# DIP_Switch.net
KiCad netlist of a schematic drawn in Altium Designer
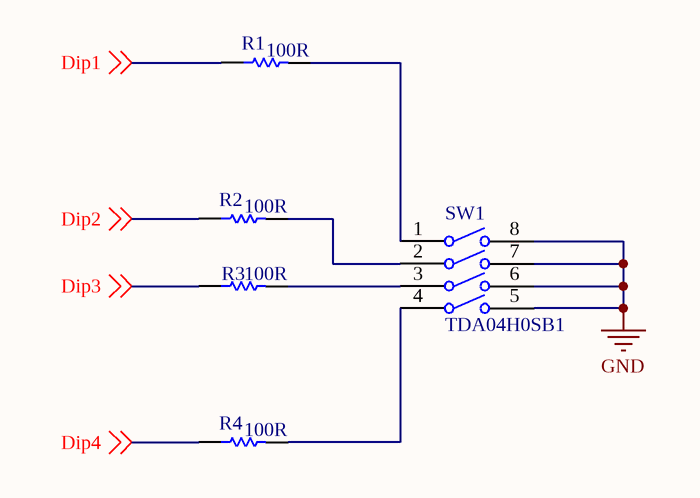
[diagram p0: DIP Switch.SchDoc]

(export (version "E")
  (design (tool "Eeschema 10.0.6"))
  (components
    (comp (ref "R1")
      (value "100R")
      (footprint "RESC0805(2012)_N")
      (description "120R 0.125W 5% 0805 (2012 Metric)  SMD")
      (fields (field (name "TOLERANCE") "5 %") (field (name "POWER") "0.125 W"))
      (libsource (lib "Husky Robotics Standard Library 2019-2020") (part "120R 5% 0805"))
    )
    (comp (ref "R2")
      (value "100R")
      (footprint "RESC0805(2012)_N")
      (description "120R 0.125W 5% 0805 (2012 Metric)  SMD")
      (fields (field (name "TOLERANCE") "5 %") (field (name "POWER") "0.125 W"))
      (libsource (lib "Husky Robotics Standard Library 2019-2020") (part "120R 5% 0805"))
    )
    (comp (ref "R3")
      (value "100R")
      (footprint "RESC0805(2012)_N")
      (description "120R 0.125W 5% 0805 (2012 Metric)  SMD")
      (fields (field (name "TOLERANCE") "5 %") (field (name "POWER") "0.125 W"))
      (libsource (lib "Husky Robotics Standard Library 2019-2020") (part "120R 5% 0805"))
    )
    (comp (ref "R4")
      (value "100R")
      (footprint "RESC0805(2012)_N")
      (description "120R 0.125W 5% 0805 (2012 Metric)  SMD")
      (fields (field (name "TOLERANCE") "5 %") (field (name "POWER") "0.125 W"))
      (libsource (lib "Husky Robotics Standard Library 2019-2020") (part "120R 5% 0805"))
    )
    (comp (ref "SW1")
      (value "TDA04H0SB1")
      (footprint "CKCP-TDA04H0SB1R_V")
      (libsource (lib "Husky Robotics Standard Library 2019-2020") (part "SMD Half-Pitch Dip Switch Array"))
    )
  )
  (nets
    (net (code "1") (name "Dip1") (class "Default")
      (node (ref "R1") (pin "1") (pinfunction "1_1") (pintype "passive"))
    )
    (net (code "2") (name "Dip2") (class "Default")
      (node (ref "R2") (pin "1") (pinfunction "1_1") (pintype "passive"))
    )
    (net (code "3") (name "Dip3") (class "Default")
      (node (ref "R3") (pin "1") (pinfunction "1_1") (pintype "passive"))
    )
    (net (code "4") (name "Dip4") (class "Default")
      (node (ref "R4") (pin "1") (pinfunction "1_1") (pintype "passive"))
    )
    (net (code "5") (name "GND") (class "Default")
      (node (ref "SW1") (pin "5") (pinfunction "5_5") (pintype "passive"))
      (node (ref "SW1") (pin "6") (pinfunction "6_6") (pintype "passive"))
      (node (ref "SW1") (pin "7") (pinfunction "7_7") (pintype "passive"))
      (node (ref "SW1") (pin "8") (pinfunction "8_8") (pintype "passive"))
    )
    (net (code "6") (name "Net-(R1-Pad2)") (class "Default")
      (node (ref "R1") (pin "2") (pinfunction "2_2") (pintype "passive"))
      (node (ref "SW1") (pin "1") (pinfunction "1_1") (pintype "passive"))
    )
    (net (code "7") (name "Net-(R2-Pad2)") (class "Default")
      (node (ref "R2") (pin "2") (pinfunction "2_2") (pintype "passive"))
      (node (ref "SW1") (pin "2") (pinfunction "2_2") (pintype "passive"))
    )
    (net (code "8") (name "Net-(R3-Pad2)") (class "Default")
      (node (ref "R3") (pin "2") (pinfunction "2_2") (pintype "passive"))
      (node (ref "SW1") (pin "3") (pinfunction "3_3") (pintype "passive"))
    )
    (net (code "9") (name "Net-(R4-Pad2)") (class "Default")
      (node (ref "R4") (pin "2") (pinfunction "2_2") (pintype "passive"))
      (node (ref "SW1") (pin "4") (pinfunction "4_4") (pintype "passive"))
    )
  )
)
